# schematic.net
KiCad netlist of a schematic drawn in Altium Designer
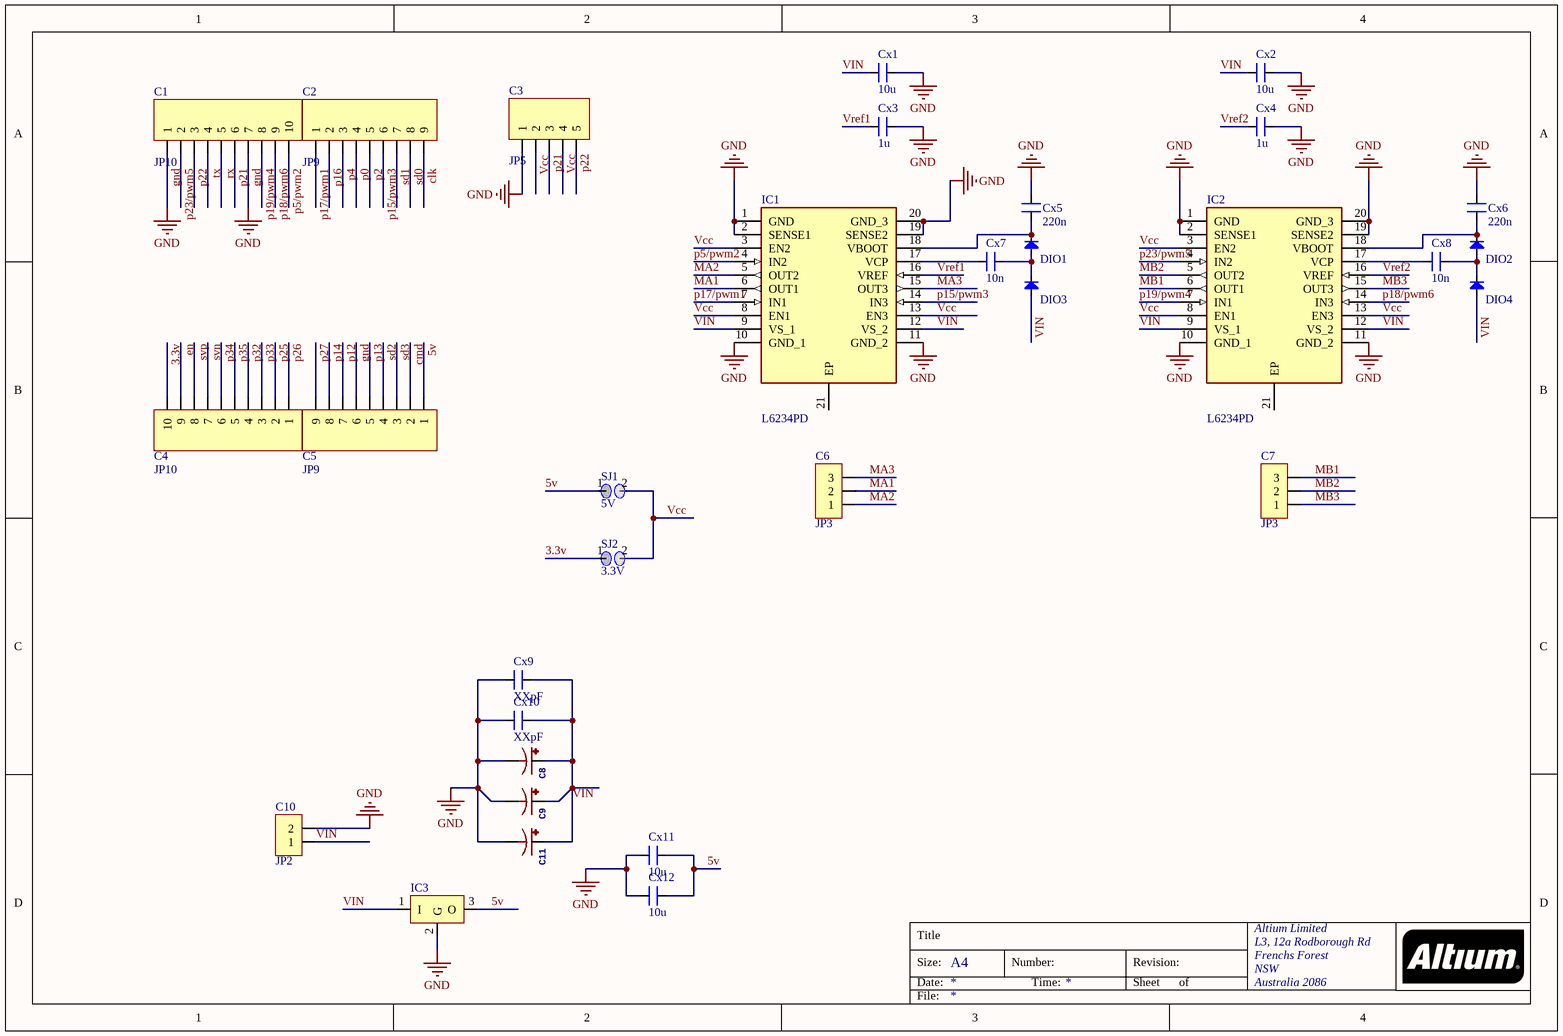
[diagram p0: schematic.SchDoc]

(export (version "E")
  (design (tool "Eeschema 10.0.6"))
  (components
    (comp (ref "C1")
      (value "JP10")
      (footprint "JP10-C1T")
      (description "WR-PHD 2.54 mm Angled Socket Header")
      (fields
        (field (name "MANUFACTURER") "Würth Elektronik eiSos GmbH")
        (field (name "PARTNO") "613010143121")
        (field (name "CREATED BY") "Karrer Zheng")
      )
      (libsource (lib "") (part "JP10_1"))
    )
    (comp (ref "C2")
      (value "JP9")
      (footprint "JP9-C1T")
      (description "WR-PHD 2.54 mm Angled Socket Header")
      (fields
        (field (name "MANUFACTURER") "Würth Elektronik eiSos GmbH")
        (field (name "PARTNO") "613009143121")
        (field (name "CREATED BY") "Karrer Zheng")
      )
      (libsource (lib "") (part "JP9_1"))
    )
    (comp (ref "C3")
      (value "JP5")
      (footprint "JP5-D1T")
      (description "WR-PHD 2.54 mm Angled Socket Header")
      (fields
        (field (name "MANUFACTURER") "Würth Elektronik eiSos GmbH")
        (field (name "PARTNO") "613005143121")
        (field (name "CREATED BY") "Karrer Zheng")
      )
      (libsource (lib "LIBRARY") (part "JP5"))
    )
    (comp (ref "C4")
      (value "JP10")
      (footprint "JP10-C1T")
      (description "WR-PHD 2.54 mm Angled Socket Header")
      (fields
        (field (name "MANUFACTURER") "Würth Elektronik eiSos GmbH")
        (field (name "PARTNO") "613010143121")
        (field (name "CREATED BY") "Karrer Zheng")
      )
      (libsource (lib "LIBRARY") (part "JP10"))
    )
    (comp (ref "C5")
      (value "JP9")
      (footprint "JP9-C1T")
      (description "WR-PHD 2.54 mm Angled Socket Header")
      (fields
        (field (name "MANUFACTURER") "Würth Elektronik eiSos GmbH")
        (field (name "PARTNO") "613009143121")
        (field (name "CREATED BY") "Karrer Zheng")
      )
      (libsource (lib "LIBRARY") (part "JP9"))
    )
    (comp (ref "C6")
      (value "JP3")
      (footprint "JP3-D1C")
      (description "WR-PHD 2.54 mm Angled Socket Header")
      (fields
        (field (name "MANUFACTURER") "Würth Elektronik eiSos GmbH")
        (field (name "PARTNO") "613003143121")
        (field (name "CREATED BY") "Karrer Zheng")
      )
      (libsource (lib "LIBRARY") (part "JP3"))
    )
    (comp (ref "C7")
      (value "JP3")
      (footprint "JP3-D1C")
      (description "WR-PHD 2.54 mm Angled Socket Header")
      (fields
        (field (name "MANUFACTURER") "Würth Elektronik eiSos GmbH")
        (field (name "PARTNO") "613003143121")
        (field (name "CREATED BY") "Karrer Zheng")
      )
      (libsource (lib "LIBRARY") (part "JP3"))
    )
    (comp (ref "C8")
      (value "~")
      (footprint "EIA3528")
      (libsource (lib "SparkFun-Capacitors") (part "47UF-POLAR-EIA3528-10V-10%"))
    )
    (comp (ref "C9")
      (value "~")
      (footprint "EIA3528")
      (libsource (lib "SparkFun-Capacitors") (part "47UF-POLAR-EIA3528-10V-10%"))
    )
    (comp (ref "C10")
      (value "JP2")
      (footprint "JP2-D1C")
      (description "WR-PHD 2.54 mm Angled Socket Header")
      (fields
        (field (name "MANUFACTURER") "Würth Elektronik eiSos GmbH")
        (field (name "PARTNO") "613002143121")
        (field (name "CREATED BY") "Karrer Zheng")
      )
      (libsource (lib "LIBRARY") (part "JP2"))
    )
    (comp (ref "C11")
      (value "~")
      (footprint "EIA3528")
      (libsource (lib "SparkFun-Capacitors") (part "47UF-POLAR-EIA3528-10V-10%"))
    )
    (comp (ref "Cx1") (value "10u") (footprint "CN-SMD-0603") (libsource (lib "LIBRARY") (part "CN")))
    (comp (ref "Cx2") (value "10u") (footprint "CN-SMD-0603") (libsource (lib "LIBRARY") (part "CN")))
    (comp (ref "Cx3") (value "1u") (footprint "CN-SMD-0603") (libsource (lib "LIBRARY") (part "CN")))
    (comp (ref "Cx4") (value "1u") (footprint "CN-SMD-0603") (libsource (lib "LIBRARY") (part "CN")))
    (comp (ref "Cx5") (value "220n") (footprint "CN-SMD-0603") (libsource (lib "LIBRARY") (part "CN")))
    (comp (ref "Cx6") (value "220n") (footprint "CN-SMD-0603") (libsource (lib "LIBRARY") (part "CN")))
    (comp (ref "Cx7") (value "10n") (footprint "CN-SMD-0603") (libsource (lib "LIBRARY") (part "CN")))
    (comp (ref "Cx8") (value "10n") (footprint "CN-SMD-0603") (libsource (lib "LIBRARY") (part "CN")))
    (comp (ref "Cx9") (value "XXpF") (footprint "CN-SMD-1206") (libsource (lib "LIBRARY") (part "CN")))
    (comp (ref "Cx10") (value "XXpF") (footprint "CN-SMD-1206") (libsource (lib "LIBRARY") (part "CN")))
    (comp (ref "Cx11") (value "10u") (footprint "CN-SMD-0603") (libsource (lib "LIBRARY") (part "CN")))
    (comp (ref "Cx12") (value "10u") (footprint "CN-SMD-0603") (libsource (lib "LIBRARY") (part "CN")))
    (comp (ref "DIO1")
      (value "Diode SMD")
      (footprint "DIO-SMD-123")
      (description "Default Diode")
      (fields (field (name "PUBLISHER") "Altium Limited"))
      (libsource (lib "LIBRARY") (part "Diode SMD"))
    )
    (comp (ref "DIO2")
      (value "Diode SMD")
      (footprint "DIO-SMD-123")
      (description "Default Diode")
      (fields (field (name "PUBLISHER") "Altium Limited"))
      (libsource (lib "LIBRARY") (part "Diode SMD"))
    )
    (comp (ref "DIO3")
      (value "Diode SMD")
      (footprint "DIO-SMD-123")
      (description "Default Diode")
      (fields (field (name "PUBLISHER") "Altium Limited"))
      (libsource (lib "LIBRARY") (part "Diode SMD"))
    )
    (comp (ref "DIO4")
      (value "Diode SMD")
      (footprint "DIO-SMD-123")
      (description "Default Diode")
      (fields (field (name "PUBLISHER") "Altium Limited"))
      (libsource (lib "LIBRARY") (part "Diode SMD"))
    )
    (comp (ref "IC1")
      (value "L6234PD")
      (footprint "SamacSys:SOIC127P1420X360-21N")
      (description "Integrated Circuit")
      (fields (field (name "MOUSER PART NUMBER") "511-L6234PD") (field (name "RS PART NUMBER") "0456444P"))
      (libsource (lib "*") (part "L6234PD"))
    )
    (comp (ref "IC2")
      (value "L6234PD")
      (footprint "SamacSys:SOIC127P1420X360-21N")
      (description "Integrated Circuit")
      (fields (field (name "MOUSER PART NUMBER") "511-L6234PD") (field (name "RS PART NUMBER") "0456444P"))
      (libsource (lib "*") (part "L6234PD"))
    )
    (comp (ref "IC3")
      (value "LM78xx")
      (footprint "TO252-123")
      (description "Positive Voltage Regulator")
      (fields (field (name "PUBLISHER") "Altium Limited"))
      (libsource (lib "LIBRARY") (part "LM78xx"))
    )
    (comp (ref "SJ1")
      (value "5V")
      (footprint "SJ-SMD")
      (libsource (lib "ABC_MAKER_VERSION2") (part "SJ-SMD"))
    )
    (comp (ref "SJ2")
      (value "3.3V")
      (footprint "SJ-SMD")
      (libsource (lib "ABC_MAKER_VERSION2") (part "SJ-SMD"))
    )
  )
  (nets
    (net (code "1") (name "/3.3v") (class "Default")
      (node (ref "C4") (pin "10") (pinfunction "10_10") (pintype "passive"))
      (node (ref "SJ2") (pin "1") (pintype "passive"))
    )
    (net (code "2") (name "/5v") (class "Default")
      (node (ref "C5") (pin "1") (pinfunction "1_1") (pintype "passive"))
      (node (ref "Cx11") (pin "2") (pinfunction "2_2") (pintype "passive"))
      (node (ref "Cx12") (pin "2") (pinfunction "2_2") (pintype "passive"))
      (node (ref "IC3") (pin "3") (pinfunction "O_3") (pintype "power_in"))
      (node (ref "SJ1") (pin "1") (pintype "passive"))
    )
    (net (code "3") (name "/MA1") (class "Default")
      (node (ref "C6") (pin "2") (pinfunction "2_2") (pintype "passive"))
      (node (ref "IC1") (pin "6") (pinfunction "OUT1_6") (pintype "output"))
    )
    (net (code "4") (name "/MA2") (class "Default")
      (node (ref "C6") (pin "1") (pinfunction "1_1") (pintype "passive"))
      (node (ref "IC1") (pin "5") (pinfunction "OUT2_5") (pintype "output"))
    )
    (net (code "5") (name "/MA3") (class "Default")
      (node (ref "C6") (pin "3") (pinfunction "3_3") (pintype "passive"))
      (node (ref "IC1") (pin "15") (pinfunction "OUT3_15") (pintype "output"))
    )
    (net (code "6") (name "/MB1") (class "Default")
      (node (ref "C7") (pin "3") (pinfunction "3_3") (pintype "passive"))
      (node (ref "IC2") (pin "6") (pinfunction "OUT1_6") (pintype "output"))
    )
    (net (code "7") (name "/MB2") (class "Default")
      (node (ref "C7") (pin "2") (pinfunction "2_2") (pintype "passive"))
      (node (ref "IC2") (pin "5") (pinfunction "OUT2_5") (pintype "output"))
    )
    (net (code "8") (name "/MB3") (class "Default")
      (node (ref "C7") (pin "1") (pinfunction "1_1") (pintype "passive"))
      (node (ref "IC2") (pin "15") (pinfunction "OUT3_15") (pintype "output"))
    )
    (net (code "9") (name "/VIN") (class "Default")
      (node (ref "C10") (pin "1") (pinfunction "1_1") (pintype "passive"))
      (node (ref "C11") (pin "A") (pinfunction "+_A") (pintype "passive"))
      (node (ref "C8") (pin "A") (pinfunction "+_A") (pintype "passive"))
      (node (ref "C9") (pin "A") (pinfunction "+_A") (pintype "passive"))
      (node (ref "Cx1") (pin "1") (pinfunction "1_1") (pintype "passive"))
      (node (ref "Cx10") (pin "2") (pinfunction "2_2") (pintype "passive"))
      (node (ref "Cx2") (pin "1") (pinfunction "1_1") (pintype "passive"))
      (node (ref "Cx9") (pin "2") (pinfunction "2_2") (pintype "passive"))
      (node (ref "DIO3") (pin "1") (pinfunction "A_1") (pintype "passive"))
      (node (ref "DIO4") (pin "1") (pinfunction "A_1") (pintype "passive"))
      (node (ref "IC1") (pin "12") (pinfunction "VS_2_12") (pintype "passive"))
      (node (ref "IC1") (pin "9") (pinfunction "VS_1_9") (pintype "passive"))
      (node (ref "IC2") (pin "12") (pinfunction "VS_2_12") (pintype "passive"))
      (node (ref "IC2") (pin "9") (pinfunction "VS_1_9") (pintype "passive"))
      (node (ref "IC3") (pin "1") (pinfunction "I_1") (pintype "power_in"))
    )
    (net (code "10") (name "/Vcc") (class "Default")
      (node (ref "C3") (pin "2") (pinfunction "2_2") (pintype "passive"))
      (node (ref "C3") (pin "4") (pinfunction "4_4") (pintype "passive"))
      (node (ref "IC1") (pin "13") (pinfunction "EN3_13") (pintype "passive"))
      (node (ref "IC1") (pin "3") (pinfunction "EN2_3") (pintype "passive"))
      (node (ref "IC1") (pin "8") (pinfunction "EN1_8") (pintype "passive"))
      (node (ref "IC2") (pin "13") (pinfunction "EN3_13") (pintype "passive"))
      (node (ref "IC2") (pin "3") (pinfunction "EN2_3") (pintype "passive"))
      (node (ref "IC2") (pin "8") (pinfunction "EN1_8") (pintype "passive"))
      (node (ref "SJ1") (pin "2") (pintype "passive"))
      (node (ref "SJ2") (pin "2") (pintype "passive"))
    )
    (net (code "11") (name "/Vref1") (class "Default")
      (node (ref "Cx3") (pin "1") (pinfunction "1_1") (pintype "passive"))
      (node (ref "IC1") (pin "16") (pinfunction "VREF_16") (pintype "input"))
    )
    (net (code "12") (name "/Vref2") (class "Default")
      (node (ref "Cx4") (pin "1") (pinfunction "1_1") (pintype "passive"))
      (node (ref "IC2") (pin "16") (pinfunction "VREF_16") (pintype "input"))
    )
    (net (code "13") (name "/clk") (class "Default")
      (node (ref "C2") (pin "9") (pinfunction "9_9") (pintype "passive"))
    )
    (net (code "14") (name "/cmd") (class "Default")
      (node (ref "C5") (pin "2") (pinfunction "2_2") (pintype "passive"))
    )
    (net (code "15") (name "/en") (class "Default")
      (node (ref "C4") (pin "9") (pinfunction "9_9") (pintype "passive"))
    )
    (net (code "16") (name "/p0") (class "Default")
      (node (ref "C2") (pin "4") (pinfunction "4_4") (pintype "passive"))
    )
    (net (code "17") (name "/p2") (class "Default")
      (node (ref "C2") (pin "5") (pinfunction "5_5") (pintype "passive"))
    )
    (net (code "18") (name "/p4") (class "Default")
      (node (ref "C2") (pin "3") (pinfunction "3_3") (pintype "passive"))
    )
    (net (code "19") (name "/p5{slash}pwm2") (class "Default")
      (node (ref "C1") (pin "10") (pinfunction "10_10") (pintype "passive"))
      (node (ref "IC1") (pin "4") (pinfunction "IN2_4") (pintype "input"))
    )
    (net (code "20") (name "/p12") (class "Default")
      (node (ref "C5") (pin "7") (pinfunction "7_7") (pintype "passive"))
    )
    (net (code "21") (name "/p13") (class "Default")
      (node (ref "C5") (pin "5") (pinfunction "5_5") (pintype "passive"))
    )
    (net (code "22") (name "/p14") (class "Default")
      (node (ref "C5") (pin "8") (pinfunction "8_8") (pintype "passive"))
    )
    (net (code "23") (name "/p15{slash}pwm3") (class "Default")
      (node (ref "C2") (pin "6") (pinfunction "6_6") (pintype "passive"))
      (node (ref "IC1") (pin "14") (pinfunction "IN3_14") (pintype "input"))
    )
    (net (code "24") (name "/p16") (class "Default")
      (node (ref "C2") (pin "2") (pinfunction "2_2") (pintype "passive"))
    )
    (net (code "25") (name "/p17{slash}pwm1") (class "Default")
      (node (ref "C2") (pin "1") (pinfunction "1_1") (pintype "passive"))
      (node (ref "IC1") (pin "7") (pinfunction "IN1_7") (pintype "input"))
    )
    (net (code "26") (name "/p18{slash}pwm6") (class "Default")
      (node (ref "C1") (pin "9") (pinfunction "9_9") (pintype "passive"))
      (node (ref "IC2") (pin "14") (pinfunction "IN3_14") (pintype "input"))
    )
    (net (code "27") (name "/p19{slash}pwm4") (class "Default")
      (node (ref "C1") (pin "8") (pinfunction "8_8") (pintype "passive"))
      (node (ref "IC2") (pin "7") (pinfunction "IN1_7") (pintype "input"))
    )
    (net (code "28") (name "/p21") (class "Default")
      (node (ref "C1") (pin "6") (pinfunction "6_6") (pintype "passive"))
      (node (ref "C3") (pin "3") (pinfunction "3_3") (pintype "passive"))
    )
    (net (code "29") (name "/p22") (class "Default")
      (node (ref "C1") (pin "3") (pinfunction "3_3") (pintype "passive"))
      (node (ref "C3") (pin "5") (pinfunction "5_5") (pintype "passive"))
    )
    (net (code "30") (name "/p23{slash}pwm5") (class "Default")
      (node (ref "C1") (pin "2") (pinfunction "2_2") (pintype "passive"))
      (node (ref "IC2") (pin "4") (pinfunction "IN2_4") (pintype "input"))
    )
    (net (code "31") (name "/p25") (class "Default")
      (node (ref "C4") (pin "2") (pinfunction "2_2") (pintype "passive"))
    )
    (net (code "32") (name "/p26") (class "Default")
      (node (ref "C4") (pin "1") (pinfunction "1_1") (pintype "passive"))
    )
    (net (code "33") (name "/p27") (class "Default")
      (node (ref "C5") (pin "9") (pinfunction "9_9") (pintype "passive"))
    )
    (net (code "34") (name "/p32") (class "Default")
      (node (ref "C4") (pin "4") (pinfunction "4_4") (pintype "passive"))
    )
    (net (code "35") (name "/p33") (class "Default")
      (node (ref "C4") (pin "3") (pinfunction "3_3") (pintype "passive"))
    )
    (net (code "36") (name "/p34") (class "Default")
      (node (ref "C4") (pin "6") (pinfunction "6_6") (pintype "passive"))
    )
    (net (code "37") (name "/p35") (class "Default")
      (node (ref "C4") (pin "5") (pinfunction "5_5") (pintype "passive"))
    )
    (net (code "38") (name "/rx") (class "Default")
      (node (ref "C1") (pin "5") (pinfunction "5_5") (pintype "passive"))
    )
    (net (code "39") (name "/sd0") (class "Default")
      (node (ref "C2") (pin "8") (pinfunction "8_8") (pintype "passive"))
    )
    (net (code "40") (name "/sd1") (class "Default")
      (node (ref "C2") (pin "7") (pinfunction "7_7") (pintype "passive"))
    )
    (net (code "41") (name "/sd2") (class "Default")
      (node (ref "C5") (pin "4") (pinfunction "4_4") (pintype "passive"))
    )
    (net (code "42") (name "/sd3") (class "Default")
      (node (ref "C5") (pin "3") (pinfunction "3_3") (pintype "passive"))
    )
    (net (code "43") (name "/svn") (class "Default")
      (node (ref "C4") (pin "7") (pinfunction "7_7") (pintype "passive"))
    )
    (net (code "44") (name "/svp") (class "Default")
      (node (ref "C4") (pin "8") (pinfunction "8_8") (pintype "passive"))
    )
    (net (code "45") (name "/tx") (class "Default")
      (node (ref "C1") (pin "4") (pinfunction "4_4") (pintype "passive"))
    )
    (net (code "46") (name "GND") (class "Default")
      (node (ref "C1") (pin "1") (pinfunction "1_1") (pintype "passive"))
      (node (ref "C1") (pin "7") (pinfunction "7_7") (pintype "passive"))
      (node (ref "C10") (pin "2") (pinfunction "2_2") (pintype "passive"))
      (node (ref "C11") (pin "C") (pinfunction "-_C") (pintype "passive"))
      (node (ref "C3") (pin "1") (pinfunction "1_1") (pintype "passive"))
      (node (ref "C5") (pin "6") (pinfunction "6_6") (pintype "passive"))
      (node (ref "C8") (pin "C") (pinfunction "-_C") (pintype "passive"))
      (node (ref "C9") (pin "C") (pinfunction "-_C") (pintype "passive"))
      (node (ref "Cx1") (pin "2") (pinfunction "2_2") (pintype "passive"))
      (node (ref "Cx10") (pin "1") (pinfunction "1_1") (pintype "passive"))
      (node (ref "Cx11") (pin "1") (pinfunction "1_1") (pintype "passive"))
      (node (ref "Cx12") (pin "1") (pinfunction "1_1") (pintype "passive"))
      (node (ref "Cx2") (pin "2") (pinfunction "2_2") (pintype "passive"))
      (node (ref "Cx3") (pin "2") (pinfunction "2_2") (pintype "passive"))
      (node (ref "Cx4") (pin "2") (pinfunction "2_2") (pintype "passive"))
      (node (ref "Cx5") (pin "2") (pinfunction "2_2") (pintype "passive"))
      (node (ref "Cx6") (pin "2") (pinfunction "2_2") (pintype "passive"))
      (node (ref "Cx9") (pin "1") (pinfunction "1_1") (pintype "passive"))
      (node (ref "IC1") (pin "1") (pinfunction "GND_1") (pintype "power_in"))
      (node (ref "IC1") (pin "10") (pinfunction "GND_1_10") (pintype "power_in"))
      (node (ref "IC1") (pin "11") (pinfunction "GND_2_11") (pintype "power_in"))
      (node (ref "IC1") (pin "19") (pinfunction "SENSE2_19") (pintype "passive"))
      (node (ref "IC1") (pin "2") (pinfunction "SENSE1_2") (pintype "passive"))
      (node (ref "IC1") (pin "20") (pinfunction "GND_3_20") (pintype "power_in"))
      (node (ref "IC2") (pin "1") (pinfunction "GND_1") (pintype "power_in"))
      (node (ref "IC2") (pin "10") (pinfunction "GND_1_10") (pintype "power_in"))
      (node (ref "IC2") (pin "11") (pinfunction "GND_2_11") (pintype "power_in"))
      (node (ref "IC2") (pin "19") (pinfunction "SENSE2_19") (pintype "passive"))
      (node (ref "IC2") (pin "2") (pinfunction "SENSE1_2") (pintype "passive"))
      (node (ref "IC2") (pin "20") (pinfunction "GND_3_20") (pintype "power_in"))
      (node (ref "IC3") (pin "2") (pinfunction "G_2") (pintype "power_in"))
    )
    (net (code "47") (name "Net-(DIO1-A)") (class "Default")
      (node (ref "Cx7") (pin "2") (pinfunction "2_2") (pintype "passive"))
      (node (ref "DIO1") (pin "1") (pinfunction "A_1") (pintype "passive"))
      (node (ref "DIO3") (pin "2") (pinfunction "K_2") (pintype "passive"))
    )
    (net (code "48") (name "Net-(DIO1-K)") (class "Default")
      (node (ref "Cx5") (pin "1") (pinfunction "1_1") (pintype "passive"))
      (node (ref "DIO1") (pin "2") (pinfunction "K_2") (pintype "passive"))
      (node (ref "IC1") (pin "18") (pinfunction "VBOOT_18") (pintype "passive"))
    )
    (net (code "49") (name "Net-(DIO2-A)") (class "Default")
      (node (ref "Cx8") (pin "2") (pinfunction "2_2") (pintype "passive"))
      (node (ref "DIO2") (pin "1") (pinfunction "A_1") (pintype "passive"))
      (node (ref "DIO4") (pin "2") (pinfunction "K_2") (pintype "passive"))
    )
    (net (code "50") (name "Net-(DIO2-K)") (class "Default")
      (node (ref "Cx6") (pin "1") (pinfunction "1_1") (pintype "passive"))
      (node (ref "DIO2") (pin "2") (pinfunction "K_2") (pintype "passive"))
      (node (ref "IC2") (pin "18") (pinfunction "VBOOT_18") (pintype "passive"))
    )
    (net (code "51") (name "Net-(IC1-VCP)") (class "Default")
      (node (ref "Cx7") (pin "1") (pinfunction "1_1") (pintype "passive"))
      (node (ref "IC1") (pin "17") (pinfunction "VCP_17") (pintype "passive"))
    )
    (net (code "52") (name "Net-(IC2-VCP)") (class "Default")
      (node (ref "Cx8") (pin "1") (pinfunction "1_1") (pintype "passive"))
      (node (ref "IC2") (pin "17") (pinfunction "VCP_17") (pintype "passive"))
    )
    (net (code "53") (name "unconnected-(IC1-EP-Pad21)") (class "Default")
      (node (ref "IC1") (pin "21") (pinfunction "EP_21") (pintype "passive"))
    )
    (net (code "54") (name "unconnected-(IC2-EP-Pad21)") (class "Default")
      (node (ref "IC2") (pin "21") (pinfunction "EP_21") (pintype "passive"))
    )
  )
)
